# utils.net
KiCad netlist of a schematic drawn in Altium Designer
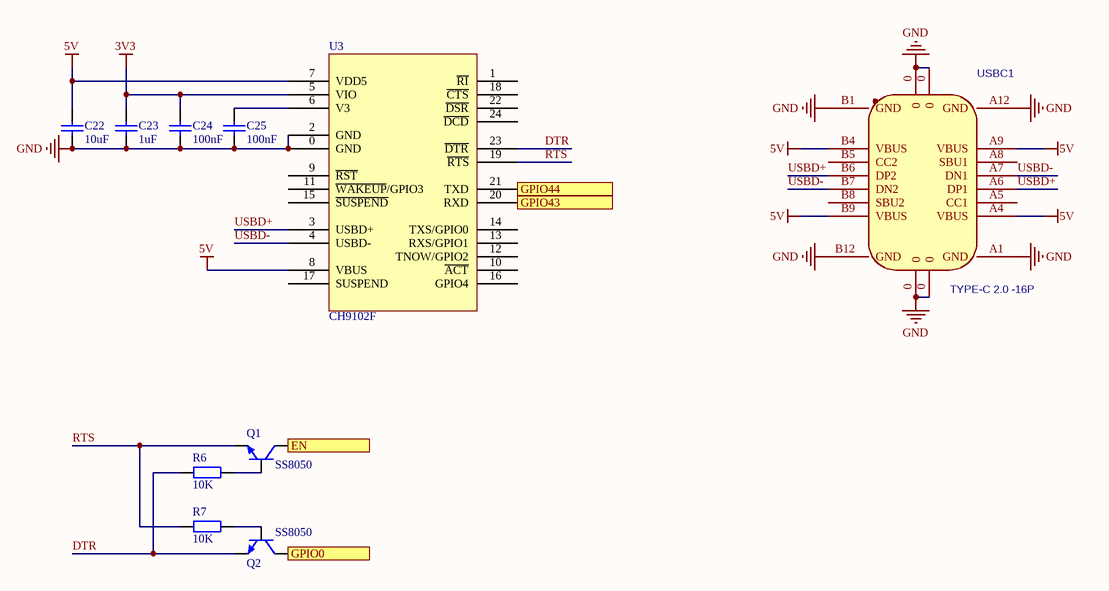
[diagram p0: utils.SchDoc]

(export (version "E")
  (design (tool "Eeschema 10.0.6"))
  (components
    (comp (ref "C22")
      (value "10uF")
      (footprint "C 0603_L")
      (description "贴片电容")
      (libsource (lib "0.1 - 电阻-电容-电感") (part "C"))
    )
    (comp (ref "C23")
      (value "1uF")
      (footprint "C 0603_L")
      (description "贴片电容")
      (libsource (lib "0.1 - 电阻-电容-电感") (part "C"))
    )
    (comp (ref "C24")
      (value "100nF")
      (footprint "C 0603_L")
      (description "贴片电容")
      (libsource (lib "0.1 - 电阻-电容-电感") (part "C"))
    )
    (comp (ref "C25")
      (value "100nF")
      (footprint "C 0603_L")
      (description "贴片电容")
      (libsource (lib "0.1 - 电阻-电容-电感") (part "C"))
    )
    (comp (ref "Q1")
      (value "SS8050")
      (footprint "SOT23-3N")
      (description "高频放大-NPN型")
      (libsource (lib "0.4 - 三极管-场效应管-可控硅") (part "8050-SMD"))
    )
    (comp (ref "Q2")
      (value "SS8050")
      (footprint "SOT23-3N")
      (description "高频放大-NPN型")
      (libsource (lib "0.4 - 三极管-场效应管-可控硅") (part "8050-SMD"))
    )
    (comp (ref "R6")
      (value "10K")
      (footprint "R 0603_L")
      (description "贴片电阻")
      (libsource (lib "0.1 - 电阻-电容-电感") (part "R"))
    )
    (comp (ref "R7")
      (value "10K")
      (footprint "R 0603_L")
      (description "贴片电阻")
      (libsource (lib "0.1 - 电阻-电容-电感") (part "R"))
    )
    (comp (ref "U3")
      (value "CH9102F")
      (footprint "QFN24")
      (description "QFN24 CH9102 CP2102替代")
      (libsource (lib "4.8 - USB转UART调试桥") (part "CH9102F"))
    )
    (comp (ref "USBC1")
      (value "TYPE-C 2.0 -16P")
      (footprint "USB-C-SMD_TYPE-C-USB-5")
      (description "USB2.0 Type-C 母座 16Pin")
      (libsource (lib "0.8 - 以太网-音频-USB插座") (part "USB2.0 Type-C 16Pin母座"))
    )
  )
  (nets
    (net (code "1") (name "/DTR") (class "Default")
      (node (ref "Q2") (pin "2") (pinfunction "E_2") (pintype "passive"))
      (node (ref "R6") (pin "1") (pinfunction "1_1") (pintype "passive"))
      (node (ref "U3") (pin "23") (pinfunction "~{DTR}_23") (pintype "passive"))
    )
    (net (code "2") (name "/EN") (class "Default")
      (node (ref "Q1") (pin "3") (pinfunction "C_3") (pintype "passive"))
    )
    (net (code "3") (name "/GPIO0") (class "Default")
      (node (ref "Q2") (pin "3") (pinfunction "C_3") (pintype "passive"))
    )
    (net (code "4") (name "/GPIO43") (class "Default")
      (node (ref "U3") (pin "20") (pinfunction "RXD_20") (pintype "passive"))
    )
    (net (code "5") (name "/GPIO44") (class "Default")
      (node (ref "U3") (pin "21") (pinfunction "TXD_21") (pintype "passive"))
    )
    (net (code "6") (name "/RTS") (class "Default")
      (node (ref "Q1") (pin "2") (pinfunction "E_2") (pintype "passive"))
      (node (ref "R7") (pin "1") (pinfunction "1_1") (pintype "passive"))
      (node (ref "U3") (pin "19") (pinfunction "~{RTS}_19") (pintype "passive"))
    )
    (net (code "7") (name "/USBD+") (class "Default")
      (node (ref "U3") (pin "3") (pinfunction "USBD+_3") (pintype "passive"))
      (node (ref "USBC1") (pin "A6") (pinfunction "DP1_A6") (pintype "passive"))
      (node (ref "USBC1") (pin "B6") (pinfunction "DP2_B6") (pintype "passive"))
    )
    (net (code "8") (name "/USBD-") (class "Default")
      (node (ref "U3") (pin "4") (pinfunction "USBD-_4") (pintype "passive"))
      (node (ref "USBC1") (pin "A7") (pinfunction "DN1_A7") (pintype "passive"))
      (node (ref "USBC1") (pin "B7") (pinfunction "DN2_B7") (pintype "passive"))
    )
    (net (code "9") (name "3V3") (class "Default")
      (node (ref "C23") (pin "2") (pinfunction "2_2") (pintype "passive"))
      (node (ref "C24") (pin "2") (pinfunction "2_2") (pintype "passive"))
      (node (ref "U3") (pin "5") (pinfunction "VIO_5") (pintype "passive"))
    )
    (net (code "10") (name "5V") (class "Default")
      (node (ref "C22") (pin "2") (pinfunction "2_2") (pintype "passive"))
      (node (ref "U3") (pin "7") (pinfunction "VDD5_7") (pintype "passive"))
      (node (ref "U3") (pin "8") (pinfunction "VBUS_8") (pintype "passive"))
      (node (ref "USBC1") (pin "A4") (pinfunction "VBUS_A4") (pintype "passive"))
      (node (ref "USBC1") (pin "A9") (pinfunction "VBUS_A9") (pintype "passive"))
      (node (ref "USBC1") (pin "B4") (pinfunction "VBUS_B4") (pintype "passive"))
      (node (ref "USBC1") (pin "B9") (pinfunction "VBUS_B9") (pintype "passive"))
    )
    (net (code "11") (name "GND") (class "Default")
      (node (ref "C22") (pin "1") (pinfunction "1_1") (pintype "passive"))
      (node (ref "C23") (pin "1") (pinfunction "1_1") (pintype "passive"))
      (node (ref "C24") (pin "1") (pinfunction "1_1") (pintype "passive"))
      (node (ref "C25") (pin "1") (pinfunction "1_1") (pintype "passive"))
      (node (ref "U3") (pin "0") (pinfunction "GND_0") (pintype "passive"))
      (node (ref "U3") (pin "2") (pinfunction "GND_2") (pintype "passive"))
      (node (ref "USBC1") (pin "0") (pinfunction "0_0") (pintype "passive"))
      (node (ref "USBC1") (pin "A1") (pinfunction "GND_A1") (pintype "passive"))
      (node (ref "USBC1") (pin "A12") (pinfunction "GND_A12") (pintype "passive"))
      (node (ref "USBC1") (pin "B1") (pinfunction "GND_B1") (pintype "passive"))
      (node (ref "USBC1") (pin "B12") (pinfunction "GND_B12") (pintype "passive"))
    )
    (net (code "12") (name "Net-(Q1-B)") (class "Default")
      (node (ref "Q1") (pin "1") (pinfunction "B_1") (pintype "passive"))
      (node (ref "R6") (pin "2") (pinfunction "2_2") (pintype "passive"))
    )
    (net (code "13") (name "Net-(Q2-B)") (class "Default")
      (node (ref "Q2") (pin "1") (pinfunction "B_1") (pintype "passive"))
      (node (ref "R7") (pin "2") (pinfunction "2_2") (pintype "passive"))
    )
    (net (code "14") (name "Net-(U3-V3)") (class "Default")
      (node (ref "C25") (pin "2") (pinfunction "2_2") (pintype "passive"))
      (node (ref "U3") (pin "6") (pinfunction "V3_6") (pintype "passive"))
    )
    (net (code "15") (name "unconnected-(U3-GPIO4-Pad16)") (class "Default")
      (node (ref "U3") (pin "16") (pinfunction "GPIO4_16") (pintype "passive"))
    )
    (net (code "16") (name "unconnected-(U3-RXS{slash}GPIO1-Pad13)") (class "Default")
      (node (ref "U3") (pin "13") (pinfunction "RXS/GPIO1_13") (pintype "passive"))
    )
    (net (code "17") (name "unconnected-(U3-SUSPEND-Pad17)") (class "Default")
      (node (ref "U3") (pin "17") (pinfunction "SUSPEND_17") (pintype "passive"))
    )
    (net (code "18") (name "unconnected-(U3-TNOW{slash}GPIO2-Pad12)") (class "Default")
      (node (ref "U3") (pin "12") (pinfunction "TNOW/GPIO2_12") (pintype "passive"))
    )
    (net (code "19") (name "unconnected-(U3-TXS{slash}GPIO0-Pad14)") (class "Default")
      (node (ref "U3") (pin "14") (pinfunction "TXS/GPIO0_14") (pintype "passive"))
    )
    (net (code "20") (name "unconnected-(U3-~{ACT}-Pad10)") (class "Default")
      (node (ref "U3") (pin "10") (pinfunction "~{ACT}_10") (pintype "passive"))
    )
    (net (code "21") (name "unconnected-(U3-~{CTS}-Pad18)") (class "Default")
      (node (ref "U3") (pin "18") (pinfunction "~{CTS}_18") (pintype "passive"))
    )
    (net (code "22") (name "unconnected-(U3-~{DCD}-Pad24)") (class "Default")
      (node (ref "U3") (pin "24") (pinfunction "~{DCD}_24") (pintype "passive"))
    )
    (net (code "23") (name "unconnected-(U3-~{DSR}-Pad22)") (class "Default")
      (node (ref "U3") (pin "22") (pinfunction "~{DSR}_22") (pintype "passive"))
    )
    (net (code "24") (name "unconnected-(U3-~{RI}-Pad1)") (class "Default")
      (node (ref "U3") (pin "1") (pinfunction "~{RI}_1") (pintype "passive"))
    )
    (net (code "25") (name "unconnected-(U3-~{RST}-Pad9)") (class "Default")
      (node (ref "U3") (pin "9") (pinfunction "~{RST}_9") (pintype "passive"))
    )
    (net (code "26") (name "unconnected-(U3-~{SUSPEND}-Pad15)") (class "Default")
      (node (ref "U3") (pin "15") (pinfunction "~{SUSPEND}_15") (pintype "passive"))
    )
    (net (code "27") (name "unconnected-(U3-~{WAKEUP}{slash}GPIO3-Pad11)") (class "Default")
      (node (ref "U3") (pin "11") (pinfunction "~{WAKEUP}/GPIO3_11") (pintype "passive"))
    )
    (net (code "28") (name "unconnected-(USBC1-CC1-PadA5)") (class "Default")
      (node (ref "USBC1") (pin "A5") (pinfunction "CC1_A5") (pintype "passive"))
    )
    (net (code "29") (name "unconnected-(USBC1-CC2-PadB5)") (class "Default")
      (node (ref "USBC1") (pin "B5") (pinfunction "CC2_B5") (pintype "passive"))
    )
    (net (code "30") (name "unconnected-(USBC1-SBU1-PadA8)") (class "Default")
      (node (ref "USBC1") (pin "A8") (pinfunction "SBU1_A8") (pintype "passive"))
    )
    (net (code "31") (name "unconnected-(USBC1-SBU2-PadB8)") (class "Default")
      (node (ref "USBC1") (pin "B8") (pinfunction "SBU2_B8") (pintype "passive"))
    )
  )
)
